# differential_driver.net
KiCad netlist of a schematic drawn in Altium Designer
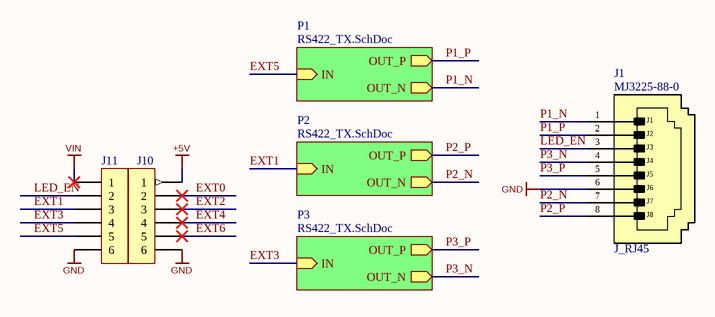
[diagram p0: differential driver.SchDoc]

(export (version "E")
  (design (tool "Eeschema 10.0.6"))
  (components
    (comp (ref "J1")
      (value "MJ3225-88-0")
      (footprint "J_RJ45_MJ3225-88-0")
      (fields
        (field (name "SCH_FOOTPRINT") "J_RJ45")
        (field (name "PART NUMBER") "J_RJ45_MJ3225-88-0")
        (field (name "MANUFACTURER") "Global Connector Technology")
        (field (name "Comment") "Modular Connector, Modular Jack, 1 x 1 (Port), 8P8C, Cat3")
      )
      (libsource (lib "Library") (part "J_RJ45"))
    )
    (comp (ref "J10")
      (value "Goldpin")
      (footprint "P_HEADER_1x6_2.54")
      (description "Pin Header")
      (fields (field (name "PART NUMBER") "P_HEADER_1x6_2.54") (field (name "MANUFACTURER") "Connfly"))
      (libsource (lib "") (part "P_HEADER_1x6_1"))
    )
    (comp (ref "J11")
      (value "Goldpin")
      (footprint "P_HEADER_1x6_2.54")
      (description "Pin Header")
      (fields (field (name "PART NUMBER") "P_HEADER_1x6_2.54") (field (name "MANUFACTURER") "Connfly"))
      (libsource (lib "Library") (part "P_HEADER_1x6"))
    )
  )
  (nets
    (net (code "1") (name "+5V") (class "Default")
      (node (ref "J10") (pin "1") (pinfunction "1_1") (pintype "output"))
    )
    (net (code "2") (name "/EXT0") (class "Default")
      (node (ref "J10") (pin "2") (pinfunction "2_2") (pintype "passive+no_connect"))
    )
    (net (code "3") (name "/EXT1") (class "Default")
      (node (ref "J11") (pin "3") (pinfunction "3_3") (pintype "passive"))
    )
    (net (code "4") (name "/EXT2") (class "Default")
      (node (ref "J10") (pin "3") (pinfunction "3_3") (pintype "passive+no_connect"))
    )
    (net (code "5") (name "/EXT3") (class "Default")
      (node (ref "J11") (pin "4") (pinfunction "4_4") (pintype "passive"))
    )
    (net (code "6") (name "/EXT4") (class "Default")
      (node (ref "J10") (pin "4") (pinfunction "4_4") (pintype "passive+no_connect"))
    )
    (net (code "7") (name "/EXT5") (class "Default")
      (node (ref "J11") (pin "5") (pinfunction "5_5") (pintype "passive"))
    )
    (net (code "8") (name "/EXT6") (class "Default")
      (node (ref "J10") (pin "5") (pinfunction "5_5") (pintype "passive+no_connect"))
    )
    (net (code "9") (name "/LED_EN") (class "Default")
      (node (ref "J1") (pin "3") (pintype "passive"))
      (node (ref "J11") (pin "2") (pinfunction "2_2") (pintype "passive"))
    )
    (net (code "10") (name "/P1_N") (class "Default") (node (ref "J1") (pin "1") (pintype "passive")))
    (net (code "11") (name "/P1_P") (class "Default") (node (ref "J1") (pin "2") (pintype "passive")))
    (net (code "12") (name "/P2_N") (class "Default") (node (ref "J1") (pin "7") (pintype "passive")))
    (net (code "13") (name "/P2_P") (class "Default") (node (ref "J1") (pin "8") (pintype "passive")))
    (net (code "14") (name "/P3_N") (class "Default") (node (ref "J1") (pin "4") (pintype "passive")))
    (net (code "15") (name "/P3_P") (class "Default") (node (ref "J1") (pin "5") (pintype "passive")))
    (net (code "16") (name "GND") (class "Default")
      (node (ref "J1") (pin "6") (pintype "passive"))
      (node (ref "J10") (pin "6") (pinfunction "6_6") (pintype "passive"))
      (node (ref "J11") (pin "6") (pinfunction "6_6") (pintype "passive"))
    )
    (net (code "17") (name "VIN") (class "Default")
      (node (ref "J11") (pin "1") (pinfunction "1_1") (pintype "passive"))
    )
  )
)
